# MagnetSensor.net
KiCad netlist of a schematic drawn in Altium Designer
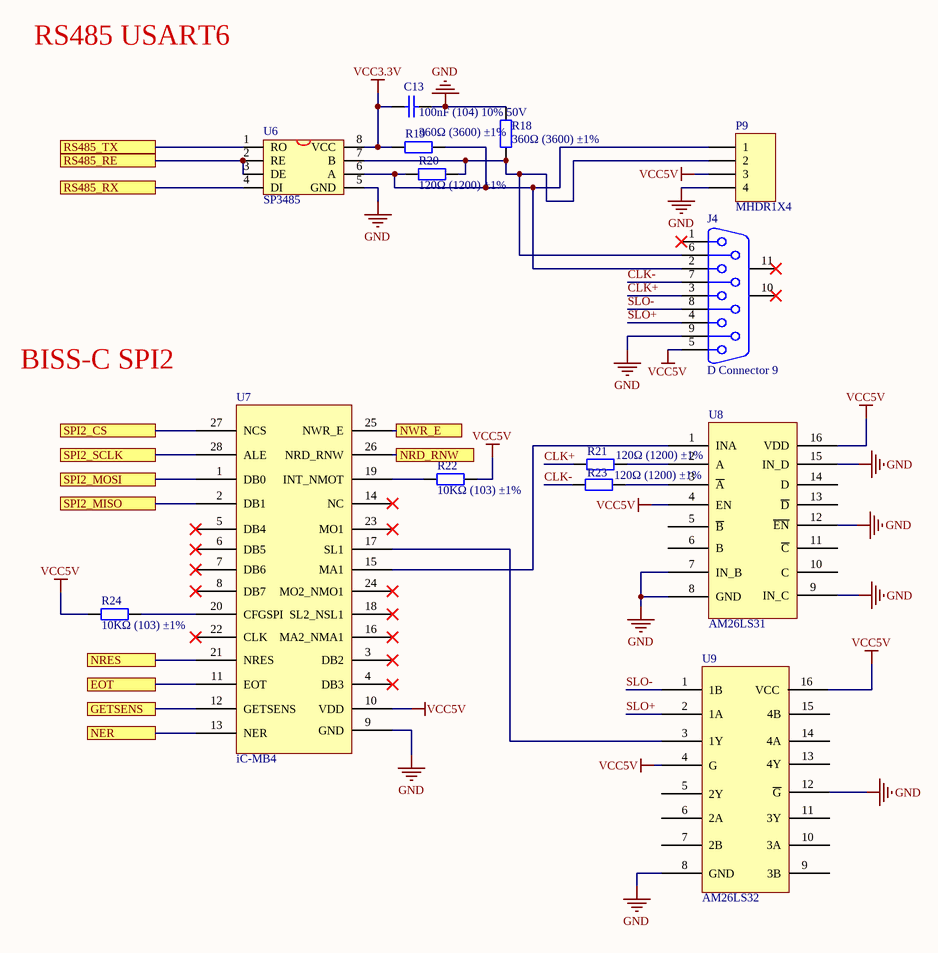
[diagram p0: MagnetSensor.SchDoc]

(export (version "E")
  (design (tool "Eeschema 10.0.6"))
  (components
    (comp (ref "C13")
      (value "100nF (104) 10% 50V")
      (footprint "0402_C")
      (description "贴片电容")
      (libsource (lib "Cap") (part "0603 100nF (104) 10% 50V"))
    )
    (comp (ref "J4")
      (value "D Connector 9")
      (footprint "DSUB1.385-2H9")
      (description "Receptacle Assembly, 9 Position, Right Angle")
      (fields (field (name "PUBLISHER") "Altium Limited"))
      (libsource (lib "Miscellaneous Connectors") (part "D Connector 9"))
    )
    (comp (ref "P9")
      (value "MHDR1X4")
      (footprint "SH1.0-4P-L")
      (description "Header, 4-Pin")
      (fields (field (name "PUBLISHER") "Altium Limited"))
      (libsource (lib "Miscellaneous Connectors") (part "MHDR1X4"))
    )
    (comp (ref "R18")
      (value "360Ω (3600) ±1%")
      (footprint "0402_R")
      (description "贴片电阻")
      (libsource (lib "") (part "0603 360Ω (3600) 1%_2"))
    )
    (comp (ref "R19")
      (value "360Ω (3600) ±1%")
      (footprint "0402_R")
      (description "贴片电阻")
      (libsource (lib "") (part "0603 360Ω (3600) 1%_1"))
    )
    (comp (ref "R20")
      (value "120Ω (1200) ±1%")
      (footprint "0402_R")
      (description "贴片电阻")
      (libsource (lib "RES") (part "0603 120Ω (1200) 1%"))
    )
    (comp (ref "R21")
      (value "120Ω (1200) ±1%")
      (footprint "0402_R")
      (description "贴片电阻")
      (libsource (lib "RES") (part "0603 360Ω (3600) 1%"))
    )
    (comp (ref "R22")
      (value "10KΩ (103) ±1%")
      (footprint "0402_R")
      (description "贴片电阻")
      (libsource (lib "RES") (part "0603 360Ω (3600) 1%"))
    )
    (comp (ref "R23")
      (value "120Ω (1200) ±1%")
      (footprint "0402_R")
      (description "贴片电阻")
      (libsource (lib "RES") (part "0603 360Ω (3600) 1%"))
    )
    (comp (ref "R24")
      (value "10KΩ (103) ±1%")
      (footprint "0402_R")
      (description "贴片电阻")
      (libsource (lib "RES") (part "0603 360Ω (3600) 1%"))
    )
    (comp (ref "U6") (value "SP3485") (footprint "SOP-8") (libsource (lib "STM32F429_F746") (part "MAX3485")))
    (comp (ref "U7")
      (value "iC-MB4")
      (footprint "QFN-28_5x5x05P")
      (description "SPI转BiSS主站芯片")
      (libsource (lib "CAS") (part "iC-MB4"))
    )
    (comp (ref "U8")
      (value "AM26LS31")
      (footprint "SO-16_N")
      (description "AM32LS31 单端转差分芯片")
      (libsource (lib "CAS") (part "AM26LS31"))
    )
    (comp (ref "U9")
      (value "AM26LS32")
      (footprint "SO-16_N")
      (description "AM26LS32 差分转单端")
      (libsource (lib "CAS") (part "AM26LS32"))
    )
  )
  (nets
    (net (code "1") (name "/CLK+") (class "Default")
      (node (ref "J4") (pin "3") (pinfunction "3_3") (pintype "passive"))
      (node (ref "R21") (pin "2") (pinfunction "2_2") (pintype "passive"))
    )
    (net (code "2") (name "/CLK-") (class "Default")
      (node (ref "J4") (pin "7") (pinfunction "7_7") (pintype "passive"))
      (node (ref "R23") (pin "2") (pinfunction "2_2") (pintype "passive"))
    )
    (net (code "3") (name "/EOT") (class "Default")
      (node (ref "U7") (pin "11") (pinfunction "EOT_11") (pintype "passive"))
    )
    (net (code "4") (name "/GETSENS") (class "Default")
      (node (ref "U7") (pin "12") (pinfunction "GETSENS_12") (pintype "passive"))
    )
    (net (code "5") (name "/NER") (class "Default")
      (node (ref "U7") (pin "13") (pinfunction "NER_13") (pintype "passive"))
    )
    (net (code "6") (name "/NRD_RNW") (class "Default")
      (node (ref "U7") (pin "26") (pinfunction "NRD_RNW_26") (pintype "passive"))
    )
    (net (code "7") (name "/NRES") (class "Default")
      (node (ref "U7") (pin "21") (pinfunction "NRES_21") (pintype "passive"))
    )
    (net (code "8") (name "/NWR_E") (class "Default")
      (node (ref "U7") (pin "25") (pinfunction "NWR_E_25") (pintype "passive"))
    )
    (net (code "9") (name "/RS485_RE") (class "Default")
      (node (ref "U6") (pin "2") (pinfunction "RE_2") (pintype "passive"))
      (node (ref "U6") (pin "3") (pinfunction "DE_3") (pintype "passive"))
    )
    (net (code "10") (name "/RS485_RX") (class "Default")
      (node (ref "U6") (pin "4") (pinfunction "DI_4") (pintype "passive"))
    )
    (net (code "11") (name "/RS485_TX") (class "Default")
      (node (ref "U6") (pin "1") (pinfunction "RO_1") (pintype "passive"))
    )
    (net (code "12") (name "/SLO+") (class "Default")
      (node (ref "J4") (pin "4") (pinfunction "4_4") (pintype "passive"))
      (node (ref "U9") (pin "2") (pinfunction "1A_2") (pintype "passive"))
    )
    (net (code "13") (name "/SLO-") (class "Default")
      (node (ref "J4") (pin "8") (pinfunction "8_8") (pintype "passive"))
      (node (ref "U9") (pin "1") (pinfunction "1B_1") (pintype "passive"))
    )
    (net (code "14") (name "/SPI2_CS") (class "Default")
      (node (ref "U7") (pin "27") (pinfunction "NCS_27") (pintype "passive"))
    )
    (net (code "15") (name "/SPI2_MISO") (class "Default")
      (node (ref "U7") (pin "2") (pinfunction "DB1_2") (pintype "passive"))
    )
    (net (code "16") (name "/SPI2_MOSI") (class "Default")
      (node (ref "U7") (pin "1") (pinfunction "DB0_1") (pintype "passive"))
    )
    (net (code "17") (name "/SPI2_SCLK") (class "Default")
      (node (ref "U7") (pin "28") (pinfunction "ALE_28") (pintype "passive"))
    )
    (net (code "18") (name "GND") (class "Default")
      (node (ref "C13") (pin "1") (pinfunction "1_1") (pintype "passive"))
      (node (ref "J4") (pin "9") (pinfunction "9_9") (pintype "passive"))
      (node (ref "P9") (pin "4") (pinfunction "4_4") (pintype "passive"))
      (node (ref "R18") (pin "2") (pinfunction "2_2") (pintype "passive"))
      (node (ref "U6") (pin "5") (pinfunction "GND_5") (pintype "passive"))
      (node (ref "U7") (pin "9") (pinfunction "GND_9") (pintype "passive"))
      (node (ref "U8") (pin "12") (pinfunction "~{EN}_12") (pintype "passive"))
      (node (ref "U8") (pin "15") (pinfunction "IN_D_15") (pintype "passive"))
      (node (ref "U8") (pin "7") (pinfunction "IN_B_7") (pintype "passive"))
      (node (ref "U8") (pin "8") (pinfunction "GND_8") (pintype "passive"))
      (node (ref "U8") (pin "9") (pinfunction "IN_C_9") (pintype "passive"))
      (node (ref "U9") (pin "12") (pinfunction "~{G}_12") (pintype "passive"))
      (node (ref "U9") (pin "8") (pinfunction "GND_8") (pintype "passive"))
    )
    (net (code "19") (name "Net-(U6-A)") (class "Default")
      (node (ref "J4") (pin "2") (pinfunction "2_2") (pintype "passive"))
      (node (ref "P9") (pin "1") (pinfunction "1_1") (pintype "passive"))
      (node (ref "R19") (pin "2") (pinfunction "2_2") (pintype "passive"))
      (node (ref "R20") (pin "2") (pinfunction "2_2") (pintype "passive"))
      (node (ref "U6") (pin "6") (pinfunction "A_6") (pintype "passive"))
    )
    (net (code "20") (name "Net-(U6-B)") (class "Default")
      (node (ref "J4") (pin "6") (pinfunction "6_6") (pintype "passive"))
      (node (ref "P9") (pin "2") (pinfunction "2_2") (pintype "passive"))
      (node (ref "R18") (pin "1") (pinfunction "1_1") (pintype "passive"))
      (node (ref "R20") (pin "1") (pinfunction "1_1") (pintype "passive"))
      (node (ref "U6") (pin "7") (pinfunction "B_7") (pintype "passive"))
    )
    (net (code "21") (name "Net-(U7-CFGSPI)") (class "Default")
      (node (ref "R24") (pin "1") (pinfunction "1_1") (pintype "passive"))
      (node (ref "U7") (pin "20") (pinfunction "CFGSPI_20") (pintype "passive"))
    )
    (net (code "22") (name "Net-(U7-INT_NMOT)") (class "Default")
      (node (ref "R22") (pin "2") (pinfunction "2_2") (pintype "passive"))
      (node (ref "U7") (pin "19") (pinfunction "INT_NMOT_19") (pintype "passive"))
    )
    (net (code "23") (name "Net-(U7-MA1)") (class "Default")
      (node (ref "U7") (pin "15") (pinfunction "MA1_15") (pintype "passive"))
      (node (ref "U8") (pin "1") (pinfunction "INA_1") (pintype "passive"))
    )
    (net (code "24") (name "Net-(U7-SL1)") (class "Default")
      (node (ref "U7") (pin "17") (pinfunction "SL1_17") (pintype "passive"))
      (node (ref "U9") (pin "3") (pinfunction "1Y_3") (pintype "passive"))
    )
    (net (code "25") (name "Net-(U8-A)") (class "Default")
      (node (ref "R21") (pin "1") (pinfunction "1_1") (pintype "passive"))
      (node (ref "U8") (pin "2") (pinfunction "A_2") (pintype "passive"))
    )
    (net (code "26") (name "Net-(U8-~{A})") (class "Default")
      (node (ref "R23") (pin "1") (pinfunction "1_1") (pintype "passive"))
      (node (ref "U8") (pin "3") (pinfunction "~{A}_3") (pintype "passive"))
    )
    (net (code "27") (name "VCC3.3V") (class "Default")
      (node (ref "C13") (pin "2") (pinfunction "2_2") (pintype "passive"))
      (node (ref "R19") (pin "1") (pinfunction "1_1") (pintype "passive"))
      (node (ref "U6") (pin "8") (pinfunction "VCC_8") (pintype "passive"))
    )
    (net (code "28") (name "VCC5V") (class "Default")
      (node (ref "J4") (pin "5") (pinfunction "5_5") (pintype "passive"))
      (node (ref "P9") (pin "3") (pinfunction "3_3") (pintype "passive"))
      (node (ref "R22") (pin "1") (pinfunction "1_1") (pintype "passive"))
      (node (ref "R24") (pin "2") (pinfunction "2_2") (pintype "passive"))
      (node (ref "U7") (pin "10") (pinfunction "VDD_10") (pintype "passive"))
      (node (ref "U8") (pin "16") (pinfunction "VDD_16") (pintype "passive"))
      (node (ref "U8") (pin "4") (pinfunction "EN_4") (pintype "passive"))
      (node (ref "U9") (pin "16") (pinfunction "VCC_16") (pintype "passive"))
      (node (ref "U9") (pin "4") (pinfunction "G_4") (pintype "passive"))
    )
    (net (code "29") (name "unconnected-(J4-MH1-Pad10)") (class "Default")
      (node (ref "J4") (pin "10") (pinfunction "MH1_10") (pintype "passive+no_connect"))
    )
    (net (code "30") (name "unconnected-(J4-MH2-Pad11)") (class "Default")
      (node (ref "J4") (pin "11") (pinfunction "MH2_11") (pintype "passive+no_connect"))
    )
    (net (code "31") (name "unconnected-(J4-Pad1)") (class "Default")
      (node (ref "J4") (pin "1") (pinfunction "1_1") (pintype "passive+no_connect"))
    )
    (net (code "32") (name "unconnected-(U7-CLK-Pad22)") (class "Default")
      (node (ref "U7") (pin "22") (pinfunction "CLK_22") (pintype "passive+no_connect"))
    )
    (net (code "33") (name "unconnected-(U7-DB2-Pad3)") (class "Default")
      (node (ref "U7") (pin "3") (pinfunction "DB2_3") (pintype "passive+no_connect"))
    )
    (net (code "34") (name "unconnected-(U7-DB3-Pad4)") (class "Default")
      (node (ref "U7") (pin "4") (pinfunction "DB3_4") (pintype "passive+no_connect"))
    )
    (net (code "35") (name "unconnected-(U7-DB4-Pad5)") (class "Default")
      (node (ref "U7") (pin "5") (pinfunction "DB4_5") (pintype "passive+no_connect"))
    )
    (net (code "36") (name "unconnected-(U7-DB5-Pad6)") (class "Default")
      (node (ref "U7") (pin "6") (pinfunction "DB5_6") (pintype "passive+no_connect"))
    )
    (net (code "37") (name "unconnected-(U7-DB6-Pad7)") (class "Default")
      (node (ref "U7") (pin "7") (pinfunction "DB6_7") (pintype "passive+no_connect"))
    )
    (net (code "38") (name "unconnected-(U7-DB7-Pad8)") (class "Default")
      (node (ref "U7") (pin "8") (pinfunction "DB7_8") (pintype "passive+no_connect"))
    )
    (net (code "39") (name "unconnected-(U7-MA2_NMA1-Pad16)") (class "Default")
      (node (ref "U7") (pin "16") (pinfunction "MA2_NMA1_16") (pintype "passive+no_connect"))
    )
    (net (code "40") (name "unconnected-(U7-MO1-Pad23)") (class "Default")
      (node (ref "U7") (pin "23") (pinfunction "MO1_23") (pintype "passive+no_connect"))
    )
    (net (code "41") (name "unconnected-(U7-MO2_NMO1-Pad24)") (class "Default")
      (node (ref "U7") (pin "24") (pinfunction "MO2_NMO1_24") (pintype "passive+no_connect"))
    )
    (net (code "42") (name "unconnected-(U7-NC-Pad14)") (class "Default")
      (node (ref "U7") (pin "14") (pinfunction "NC_14") (pintype "passive+no_connect"))
    )
    (net (code "43") (name "unconnected-(U7-SL2_NSL1-Pad18)") (class "Default")
      (node (ref "U7") (pin "18") (pinfunction "SL2_NSL1_18") (pintype "passive+no_connect"))
    )
    (net (code "44") (name "unconnected-(U8-B-Pad6)") (class "Default")
      (node (ref "U8") (pin "6") (pinfunction "B_6") (pintype "passive"))
    )
    (net (code "45") (name "unconnected-(U8-C-Pad10)") (class "Default")
      (node (ref "U8") (pin "10") (pinfunction "C_10") (pintype "passive"))
    )
    (net (code "46") (name "unconnected-(U8-D-Pad14)") (class "Default")
      (node (ref "U8") (pin "14") (pinfunction "D_14") (pintype "passive"))
    )
    (net (code "47") (name "unconnected-(U8-~{B}-Pad5)") (class "Default")
      (node (ref "U8") (pin "5") (pinfunction "~{B}_5") (pintype "passive"))
    )
    (net (code "48") (name "unconnected-(U8-~{C}-Pad11)") (class "Default")
      (node (ref "U8") (pin "11") (pinfunction "~{C}_11") (pintype "passive"))
    )
    (net (code "49") (name "unconnected-(U8-~{D}-Pad13)") (class "Default")
      (node (ref "U8") (pin "13") (pinfunction "~{D}_13") (pintype "passive"))
    )
    (net (code "50") (name "unconnected-(U9-2A-Pad6)") (class "Default")
      (node (ref "U9") (pin "6") (pinfunction "2A_6") (pintype "passive"))
    )
    (net (code "51") (name "unconnected-(U9-2B-Pad7)") (class "Default")
      (node (ref "U9") (pin "7") (pinfunction "2B_7") (pintype "passive"))
    )
    (net (code "52") (name "unconnected-(U9-2Y-Pad5)") (class "Default")
      (node (ref "U9") (pin "5") (pinfunction "2Y_5") (pintype "passive"))
    )
    (net (code "53") (name "unconnected-(U9-3A-Pad10)") (class "Default")
      (node (ref "U9") (pin "10") (pinfunction "3A_10") (pintype "passive"))
    )
    (net (code "54") (name "unconnected-(U9-3B-Pad9)") (class "Default")
      (node (ref "U9") (pin "9") (pinfunction "3B_9") (pintype "passive"))
    )
    (net (code "55") (name "unconnected-(U9-3Y-Pad11)") (class "Default")
      (node (ref "U9") (pin "11") (pinfunction "3Y_11") (pintype "passive"))
    )
    (net (code "56") (name "unconnected-(U9-4A-Pad14)") (class "Default")
      (node (ref "U9") (pin "14") (pinfunction "4A_14") (pintype "passive"))
    )
    (net (code "57") (name "unconnected-(U9-4B-Pad15)") (class "Default")
      (node (ref "U9") (pin "15") (pinfunction "4B_15") (pintype "passive"))
    )
    (net (code "58") (name "unconnected-(U9-4Y-Pad13)") (class "Default")
      (node (ref "U9") (pin "13") (pinfunction "4Y_13") (pintype "passive"))
    )
  )
)
